# SCH_Cat-LED-Chaser_2025-11-08.net
KiCad netlist of a schematic drawn in EasyEDA
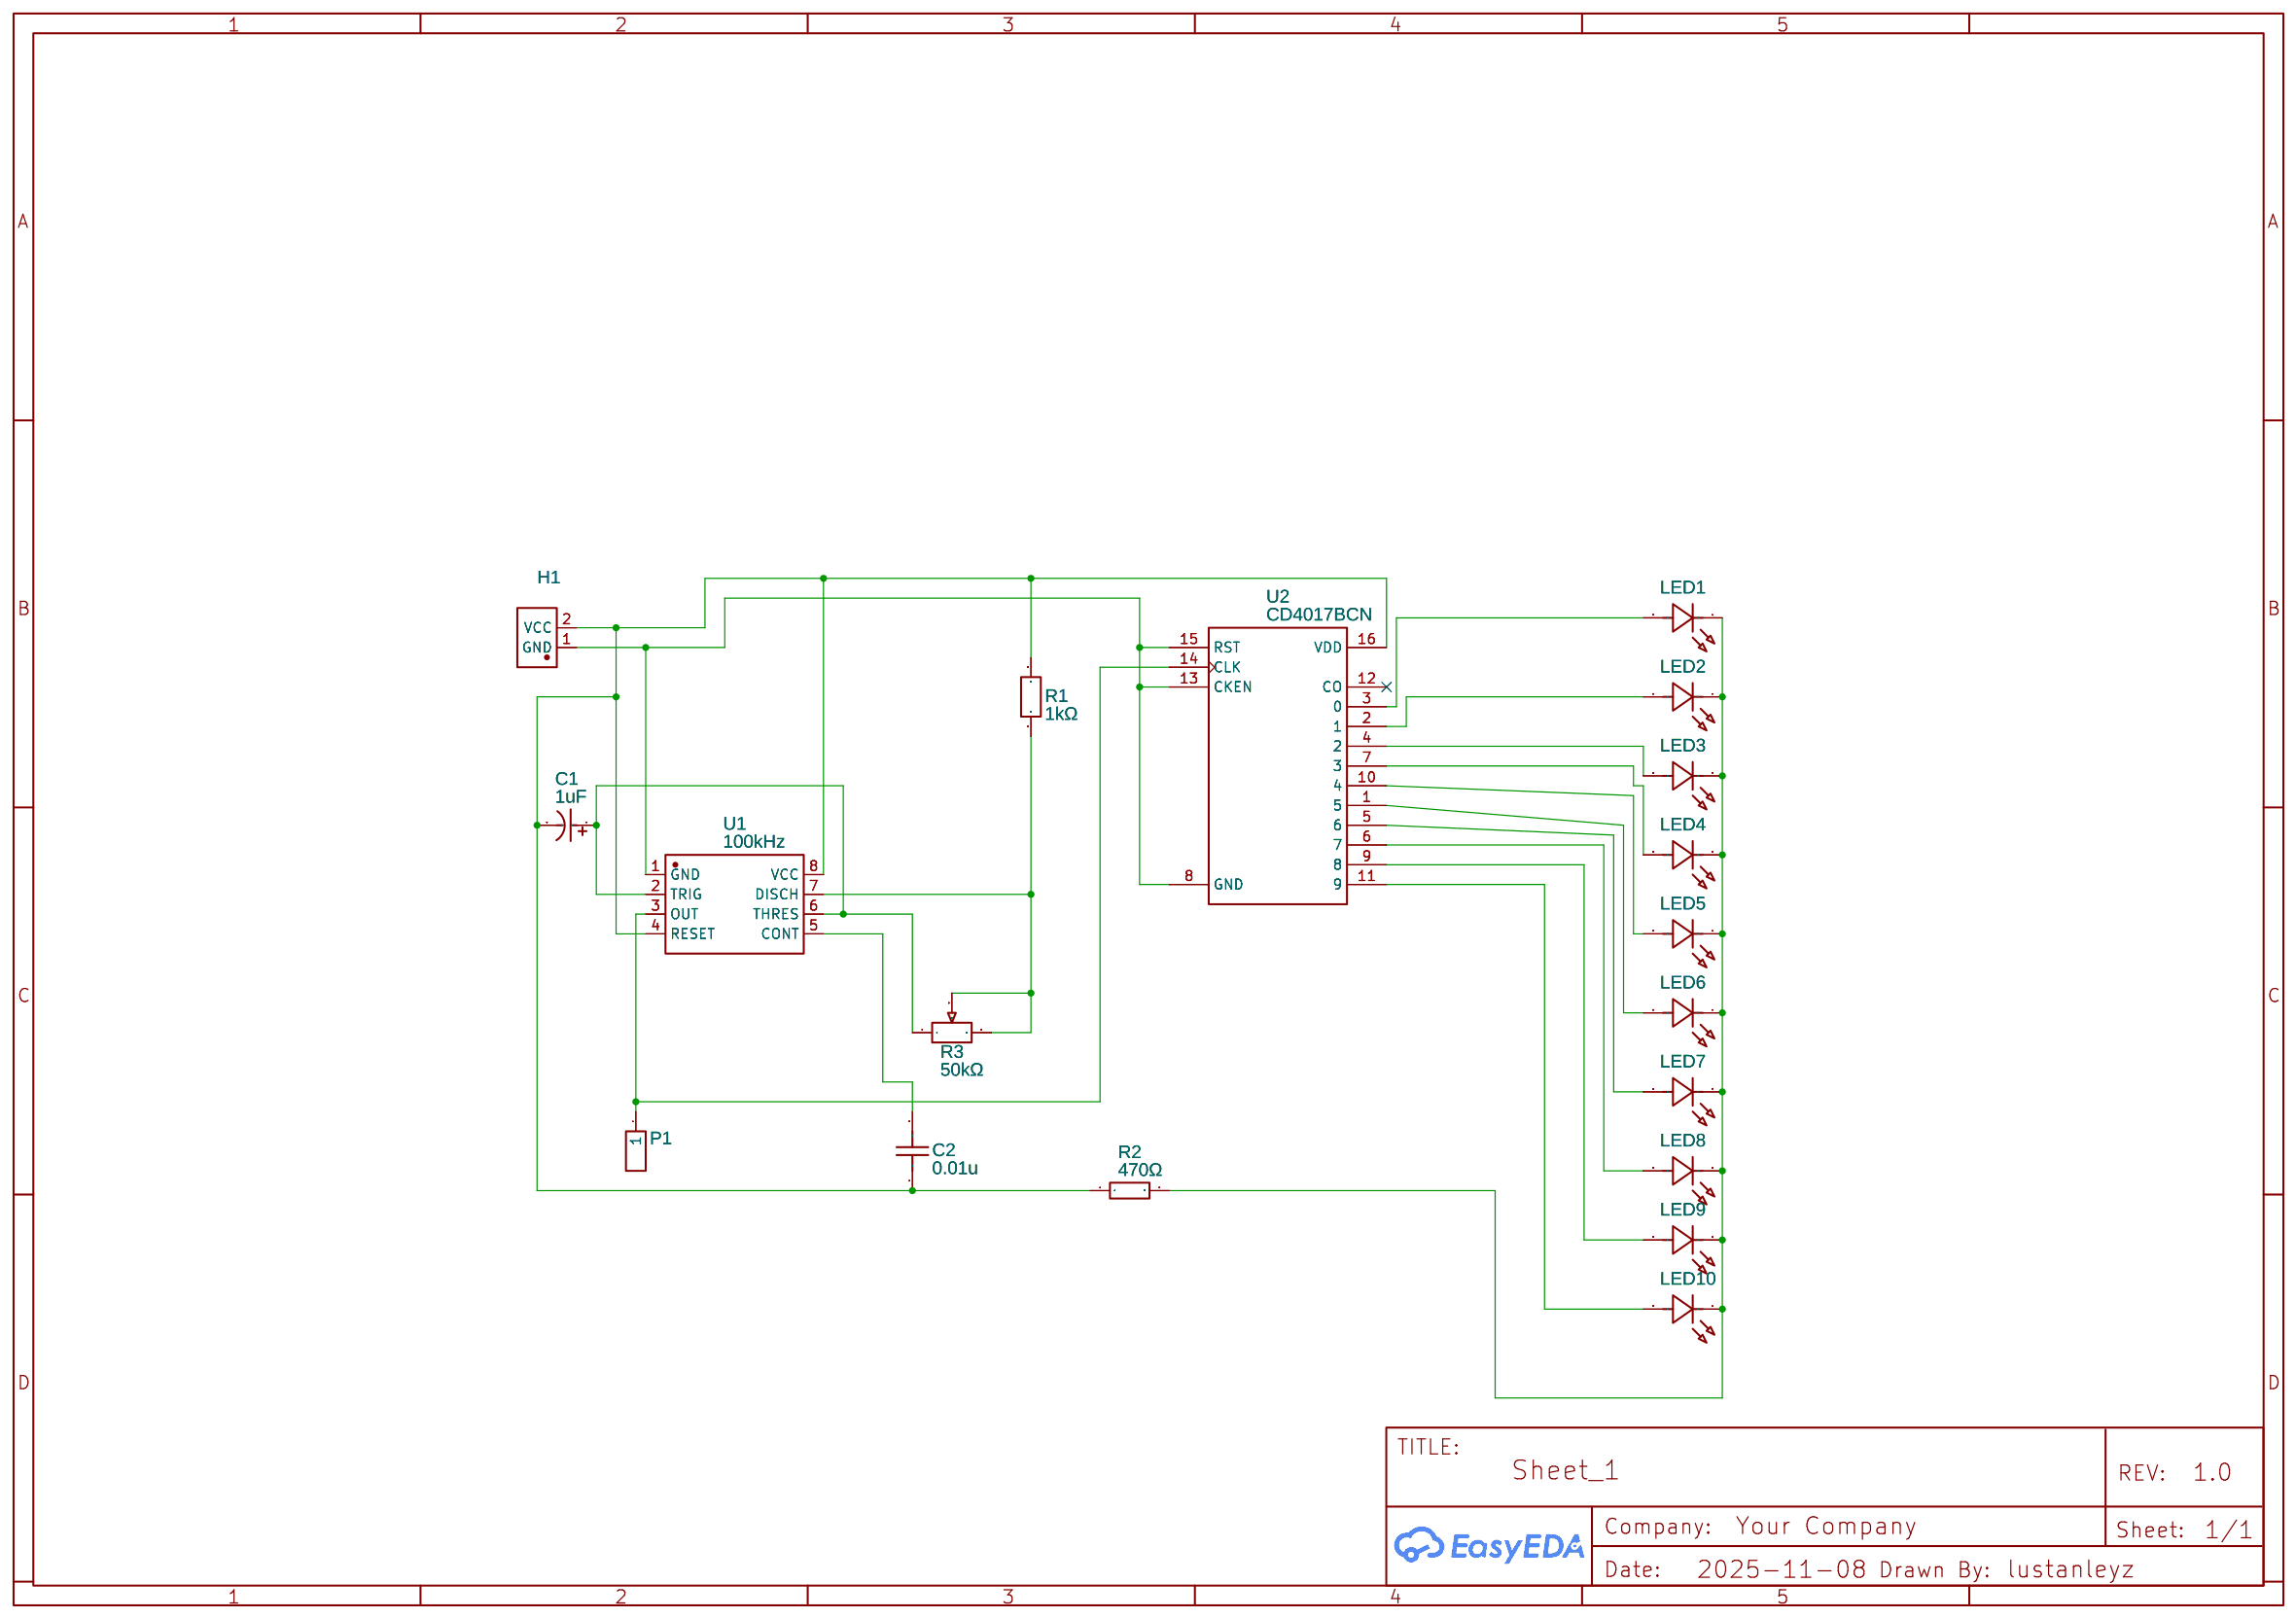
[diagram p0: schematic sheet]

(export (version "E")
  (design (tool "Eeschema 10.0.6"))
  (components
    (comp (ref "C1")
      (value "1uF")
      (fields (field (name "Manufacturer Part") "KF010M050C110A") (field (name "Manufacturer") "CapXon(丰宾)"))
      (libsource (lib "") (part "KF010M050C110A"))
    )
    (comp (ref "C2")
      (value "0.01u")
      (fields (field (name "Manufacturer Part") "N09F1B103MN0B0S0N0") (field (name "Manufacturer") "STE(松田)"))
      (libsource (lib "") (part "N09F1B103MN0B0S0N0"))
    )
    (comp (ref "H1")
      (value "PZ254V-11-02P")
      (fields (field (name "Manufacturer") "XFCN(兴飞)"))
      (libsource (lib "") (part "PZ254V-11-02P"))
    )
    (comp (ref "LED1")
      (value "XL-502UWC")
      (fields (field (name "Manufacturer") "XINGLIGHT(成兴光)"))
      (libsource (lib "") (part "XL-502UWC"))
    )
    (comp (ref "LED2")
      (value "XL-502UWC")
      (fields (field (name "Manufacturer") "XINGLIGHT(成兴光)"))
      (libsource (lib "") (part "XL-502UWC"))
    )
    (comp (ref "LED3")
      (value "XL-502UWC")
      (fields (field (name "Manufacturer") "XINGLIGHT(成兴光)"))
      (libsource (lib "") (part "XL-502UWC"))
    )
    (comp (ref "LED4")
      (value "XL-502UWC")
      (fields (field (name "Manufacturer") "XINGLIGHT(成兴光)"))
      (libsource (lib "") (part "XL-502UWC"))
    )
    (comp (ref "LED5")
      (value "XL-502UWC")
      (fields (field (name "Manufacturer") "XINGLIGHT(成兴光)"))
      (libsource (lib "") (part "XL-502UWC"))
    )
    (comp (ref "LED6")
      (value "XL-502UWC")
      (fields (field (name "Manufacturer") "XINGLIGHT(成兴光)"))
      (libsource (lib "") (part "XL-502UWC"))
    )
    (comp (ref "LED7")
      (value "XL-502UWC")
      (fields (field (name "Manufacturer") "XINGLIGHT(成兴光)"))
      (libsource (lib "") (part "XL-502UWC"))
    )
    (comp (ref "LED8")
      (value "XL-502UWC")
      (fields (field (name "Manufacturer") "XINGLIGHT(成兴光)"))
      (libsource (lib "") (part "XL-502UWC"))
    )
    (comp (ref "LED9")
      (value "XL-502UWC")
      (fields (field (name "Manufacturer") "XINGLIGHT(成兴光)"))
      (libsource (lib "") (part "XL-502UWC"))
    )
    (comp (ref "LED10")
      (value "XL-502UWC")
      (fields (field (name "Manufacturer") "XINGLIGHT(成兴光)"))
      (libsource (lib "") (part "XL-502UWC"))
    )
    (comp (ref "P1")
      (value "Header-Male-2.54_1x1")
      (fields (field (name "Manufacturer Part") "2.54-1*1P针") (field (name "Manufacturer") "BOOMELE(博穆精密)"))
      (libsource (lib "") (part "Header-Male-2.54_1x1"))
    )
    (comp (ref "R1")
      (value "1kΩ")
      (fields (field (name "Manufacturer Part") "MF1/4W-1KΩ±1%T52") (field (name "Manufacturer") "华星机电"))
      (libsource (lib "") (part "MF1/4W-1KΩ±1%T52"))
    )
    (comp (ref "R2")
      (value "470Ω")
      (fields
        (field (name "Manufacturer Part") "MFR0W4F4700A50")
        (field (name "Manufacturer") "UNI-ROYAL(厚声)")
      )
      (libsource (lib "") (part "MFR0W4F4700A50"))
    )
    (comp (ref "R3")
      (value "50kΩ")
      (fields (field (name "Manufacturer Part") "3296X-1-503") (field (name "Manufacturer") "BOCHEN(博晨)"))
      (libsource (lib "") (part "3296X-1-503_C118912"))
    )
    (comp (ref "U1")
      (value "100kHz")
      (fields (field (name "Manufacturer Part") "NE555P") (field (name "Manufacturer") "TI(德州仪器)"))
      (libsource (lib "") (part "NE555P"))
    )
    (comp (ref "U2") (value "CD4017BCN") (libsource (lib "") (part "CD4017BCN")))
  )
  (nets
    (net (code "1") (name "Net-(H1-GND)") (class "Default")
      (node (ref "H1") (pin "1") (pinfunction "GND_1") (pintype "unspecified"))
      (node (ref "U1") (pin "1") (pinfunction "GND_1") (pintype "unspecified"))
      (node (ref "U2") (pin "13") (pinfunction "CKEN_13") (pintype "unspecified"))
      (node (ref "U2") (pin "15") (pinfunction "RST_15") (pintype "unspecified"))
      (node (ref "U2") (pin "8") (pinfunction "GND_8") (pintype "passive"))
    )
    (net (code "2") (name "Net-(H1-VCC)") (class "Default")
      (node (ref "C1") (pin "2") (pinfunction "2_2") (pintype "input"))
      (node (ref "C2") (pin "1") (pinfunction "1_1") (pintype "unspecified"))
      (node (ref "H1") (pin "2") (pinfunction "VCC_2") (pintype "unspecified"))
      (node (ref "R1") (pin "2") (pinfunction "2_2") (pintype "unspecified"))
      (node (ref "R2") (pin "1") (pinfunction "1_1") (pintype "input"))
      (node (ref "U1") (pin "4") (pinfunction "RESET_4") (pintype "unspecified"))
      (node (ref "U1") (pin "8") (pinfunction "VCC_8") (pintype "unspecified"))
      (node (ref "U2") (pin "16") (pinfunction "VDD_16") (pintype "passive"))
    )
    (net (code "3") (name "Net-(LED1-A)") (class "Default")
      (node (ref "LED1") (pin "2") (pinfunction "A_2") (pintype "unspecified"))
      (node (ref "U2") (pin "3") (pinfunction "0_3") (pintype "output"))
    )
    (net (code "4") (name "Net-(LED1-K)") (class "Default")
      (node (ref "LED1") (pin "1") (pinfunction "K_1") (pintype "unspecified"))
      (node (ref "LED10") (pin "1") (pinfunction "K_1") (pintype "unspecified"))
      (node (ref "LED2") (pin "1") (pinfunction "K_1") (pintype "unspecified"))
      (node (ref "LED3") (pin "1") (pinfunction "K_1") (pintype "unspecified"))
      (node (ref "LED4") (pin "1") (pinfunction "K_1") (pintype "unspecified"))
      (node (ref "LED5") (pin "1") (pinfunction "K_1") (pintype "unspecified"))
      (node (ref "LED6") (pin "1") (pinfunction "K_1") (pintype "unspecified"))
      (node (ref "LED7") (pin "1") (pinfunction "K_1") (pintype "unspecified"))
      (node (ref "LED8") (pin "1") (pinfunction "K_1") (pintype "unspecified"))
      (node (ref "LED9") (pin "1") (pinfunction "K_1") (pintype "unspecified"))
      (node (ref "R2") (pin "2") (pinfunction "2_2") (pintype "input"))
    )
    (net (code "5") (name "Net-(LED2-A)") (class "Default")
      (node (ref "LED2") (pin "2") (pinfunction "A_2") (pintype "unspecified"))
      (node (ref "U2") (pin "2") (pinfunction "1_2") (pintype "output"))
    )
    (net (code "6") (name "Net-(LED3-A)") (class "Default")
      (node (ref "LED3") (pin "2") (pinfunction "A_2") (pintype "unspecified"))
      (node (ref "U2") (pin "4") (pinfunction "2_4") (pintype "output"))
    )
    (net (code "7") (name "Net-(LED4-A)") (class "Default")
      (node (ref "LED4") (pin "2") (pinfunction "A_2") (pintype "unspecified"))
      (node (ref "U2") (pin "7") (pinfunction "3_7") (pintype "output"))
    )
    (net (code "8") (name "Net-(LED5-A)") (class "Default")
      (node (ref "LED5") (pin "2") (pinfunction "A_2") (pintype "unspecified"))
      (node (ref "U2") (pin "10") (pinfunction "4_10") (pintype "output"))
    )
    (net (code "9") (name "Net-(LED6-A)") (class "Default")
      (node (ref "LED6") (pin "2") (pinfunction "A_2") (pintype "unspecified"))
      (node (ref "U2") (pin "1") (pinfunction "5_1") (pintype "output"))
    )
    (net (code "10") (name "Net-(LED7-A)") (class "Default")
      (node (ref "LED7") (pin "2") (pinfunction "A_2") (pintype "unspecified"))
      (node (ref "U2") (pin "5") (pinfunction "6_5") (pintype "output"))
    )
    (net (code "11") (name "Net-(LED8-A)") (class "Default")
      (node (ref "LED8") (pin "2") (pinfunction "A_2") (pintype "unspecified"))
      (node (ref "U2") (pin "6") (pinfunction "7_6") (pintype "output"))
    )
    (net (code "12") (name "Net-(LED9-A)") (class "Default")
      (node (ref "LED9") (pin "2") (pinfunction "A_2") (pintype "unspecified"))
      (node (ref "U2") (pin "9") (pinfunction "8_9") (pintype "output"))
    )
    (net (code "13") (name "Net-(LED10-A)") (class "Default")
      (node (ref "LED10") (pin "2") (pinfunction "A_2") (pintype "unspecified"))
      (node (ref "U2") (pin "11") (pinfunction "9_11") (pintype "output"))
    )
    (net (code "14") (name "Net-(U1-CONT)") (class "Default")
      (node (ref "C2") (pin "2") (pinfunction "2_2") (pintype "unspecified"))
      (node (ref "U1") (pin "5") (pinfunction "CONT_5") (pintype "unspecified"))
    )
    (net (code "15") (name "Net-(U1-DISCH)") (class "Default")
      (node (ref "R1") (pin "1") (pinfunction "1_1") (pintype "unspecified"))
      (node (ref "R3") (pin "2") (pinfunction "2_2") (pintype "input"))
      (node (ref "R3") (pin "3") (pinfunction "3_3") (pintype "input"))
      (node (ref "U1") (pin "7") (pinfunction "DISCH_7") (pintype "unspecified"))
    )
    (net (code "16") (name "Net-(U1-OUT)") (class "Default")
      (node (ref "P1") (pin "1") (pinfunction "1_1") (pintype "input"))
      (node (ref "U1") (pin "3") (pinfunction "OUT_3") (pintype "unspecified"))
      (node (ref "U2") (pin "14") (pinfunction "CLK_14") (pintype "unspecified"))
    )
    (net (code "17") (name "Net-(U1-THRES)") (class "Default")
      (node (ref "C1") (pin "1") (pinfunction "1_1") (pintype "input"))
      (node (ref "R3") (pin "1") (pinfunction "1_1") (pintype "input"))
      (node (ref "U1") (pin "2") (pinfunction "TRIG_2") (pintype "unspecified"))
      (node (ref "U1") (pin "6") (pinfunction "THRES_6") (pintype "unspecified"))
    )
    (net (code "18") (name "unconnected-(U2-CO-Pad12)") (class "Default")
      (node (ref "U2") (pin "12") (pinfunction "CO_12") (pintype "output+no_connect"))
    )
  )
)
